# rail_crossing.net
KiCad netlist of a schematic drawn in EAGLE
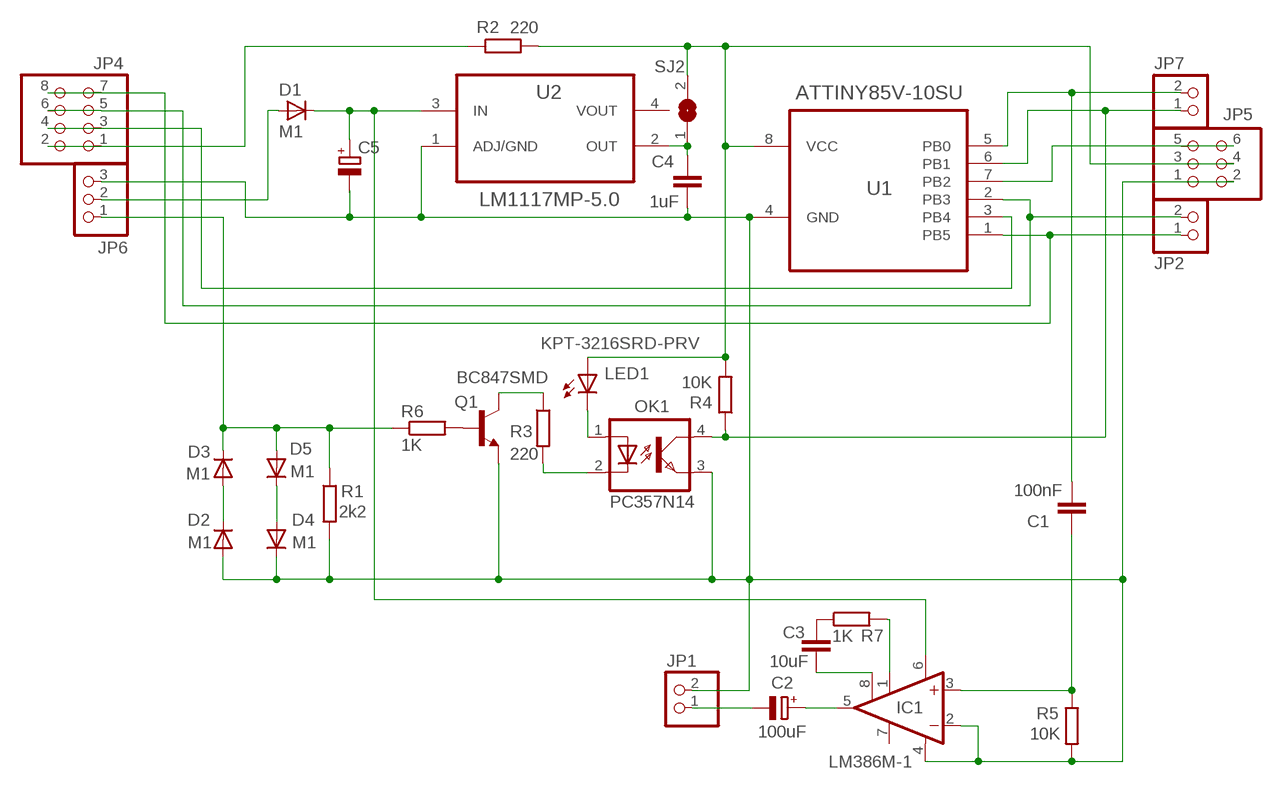
[diagram p0: schematic, sheet 1]

(export (version "E")
  (design (tool "Eeschema 10.0.6"))
  (components
    (comp (ref "C1")
      (value "100nF")
      (footprint "eagle-import:C1206")
      (libsource (lib "eagle-import") (part "C-EUC1206"))
    )
    (comp (ref "C2")
      (value "100uF")
      (footprint "eagle-import:SMC_C")
      (libsource (lib "eagle-import") (part "CPOL-EUSMCC"))
    )
    (comp (ref "C3")
      (value "10uF")
      (footprint "eagle-import:C1206")
      (libsource (lib "eagle-import") (part "C-EUC1206"))
    )
    (comp (ref "C4")
      (value "1uF")
      (footprint "eagle-import:C0402")
      (libsource (lib "eagle-import") (part "C-EUC0402"))
    )
    (comp (ref "C5")
      (value "CPOL-EUSMCD")
      (footprint "eagle-import:SMC_D")
      (libsource (lib "eagle-import") (part "CPOL-EUSMCD"))
    )
    (comp (ref "D1")
      (value "M1")
      (footprint "eagle-import:SMB")
      (libsource (lib "eagle-import") (part "ES2D"))
    )
    (comp (ref "D2")
      (value "M1")
      (footprint "eagle-import:SMB")
      (libsource (lib "eagle-import") (part "ES2D"))
    )
    (comp (ref "D3")
      (value "M1")
      (footprint "eagle-import:SMB")
      (libsource (lib "eagle-import") (part "ES2D"))
    )
    (comp (ref "D4")
      (value "M1")
      (footprint "eagle-import:SMB")
      (libsource (lib "eagle-import") (part "ES2D"))
    )
    (comp (ref "D5")
      (value "M1")
      (footprint "eagle-import:SMB")
      (libsource (lib "eagle-import") (part "ES2D"))
    )
    (comp (ref "IC1")
      (value "LM386M-1")
      (footprint "eagle-import:SO08")
      (libsource (lib "eagle-import") (part "LM386?-M1"))
    )
    (comp (ref "JP1")
      (value "PINHD-1X2/90")
      (footprint "eagle-import:1X02_90")
      (libsource (lib "eagle-import") (part "PINHD-1X2/90"))
    )
    (comp (ref "JP2")
      (value "PINHD-1X2/90")
      (footprint "eagle-import:1X02_90")
      (libsource (lib "eagle-import") (part "PINHD-1X2/90"))
    )
    (comp (ref "JP4")
      (value "PINHD-2X4/90")
      (footprint "eagle-import:2X04_90")
      (libsource (lib "eagle-import") (part "PINHD-2X4/90"))
    )
    (comp (ref "JP5")
      (value "PINHD-2X3/90")
      (footprint "eagle-import:2X03_90")
      (libsource (lib "eagle-import") (part "PINHD-2X3/90"))
    )
    (comp (ref "JP6")
      (value "PINHD-1X3/90")
      (footprint "eagle-import:1X03_90")
      (libsource (lib "eagle-import") (part "PINHD-1X3/90"))
    )
    (comp (ref "JP7")
      (value "PINHD-1X2/90")
      (footprint "eagle-import:1X02_90")
      (libsource (lib "eagle-import") (part "PINHD-1X2/90"))
    )
    (comp (ref "LED1")
      (value "KPT-3216SRD-PRV")
      (footprint "eagle-import:SML1206")
      (libsource (lib "eagle-import") (part "LEDSML1206"))
    )
    (comp (ref "OK1")
      (value "PC357N14")
      (footprint "eagle-import:SMD4")
      (libsource (lib "eagle-import") (part "LTV816S"))
    )
    (comp (ref "Q1")
      (value "BC847SMD")
      (footprint "eagle-import:SOT23")
      (libsource (lib "eagle-import") (part "BC847SMD"))
    )
    (comp (ref "R1")
      (value "2k2")
      (footprint "eagle-import:R1206")
      (libsource (lib "eagle-import") (part "R-EU_R1206"))
    )
    (comp (ref "R2")
      (value "220")
      (footprint "eagle-import:R1206")
      (libsource (lib "eagle-import") (part "R-EU_R1206"))
    )
    (comp (ref "R3")
      (value "220")
      (footprint "eagle-import:R1206")
      (libsource (lib "eagle-import") (part "R-EU_R1206"))
    )
    (comp (ref "R4")
      (value "10K")
      (footprint "eagle-import:R1206")
      (libsource (lib "eagle-import") (part "R-EU_R1206"))
    )
    (comp (ref "R5")
      (value "10K")
      (footprint "eagle-import:R1206")
      (libsource (lib "eagle-import") (part "R-EU_R1206"))
    )
    (comp (ref "R6")
      (value "1K")
      (footprint "eagle-import:R1206")
      (libsource (lib "eagle-import") (part "R-EU_R1206"))
    )
    (comp (ref "R7")
      (value "1K")
      (footprint "eagle-import:M1206")
      (libsource (lib "eagle-import") (part "R-EU_M1206"))
    )
    (comp (ref "SJ2") (value "SJ") (footprint "eagle-import:SJ") (libsource (lib "eagle-import") (part "SJ")))
    (comp (ref "U1")
      (value "ATTINY85V-10SU")
      (footprint "eagle-import:SOIC127P798X216-8N")
      (libsource (lib "eagle-import") (part "ATTINY85V-10SU"))
    )
    (comp (ref "U2")
      (value "LM1117MP-5.0")
      (footprint "eagle-import:SOT230P696X180-4N")
      (libsource (lib "eagle-import") (part "LM1117MP-5.0"))
    )
  )
  (nets
    (net (code "1") (name "Net-(C2-Pad-)") (class "Default")
      (node (ref "C2") (pin "-") (pinfunction "-_-") (pintype "passive"))
      (node (ref "JP1") (pin "1") (pinfunction "1_1") (pintype "passive"))
    )
    (net (code "2") (name "Net-(C3-Pad1)") (class "Default")
      (node (ref "C3") (pin "1") (pinfunction "1_1") (pintype "passive"))
      (node (ref "R7") (pin "1") (pinfunction "1_1") (pintype "passive"))
    )
    (net (code "3") (name "Net-(C3-Pad2)") (class "Default")
      (node (ref "C3") (pin "2") (pinfunction "2_2") (pintype "passive"))
      (node (ref "IC1") (pin "8") (pinfunction "GAIN_8") (pintype "passive"))
    )
    (net (code "4") (name "Net-(D1-PadA)") (class "Default")
      (node (ref "D1") (pin "A") (pinfunction "A_A") (pintype "passive"))
      (node (ref "JP6") (pin "2") (pinfunction "2_2") (pintype "passive"))
    )
    (net (code "5") (name "Net-(D2-PadC)") (class "Default")
      (node (ref "D2") (pin "C") (pinfunction "C_C") (pintype "passive"))
      (node (ref "D3") (pin "A") (pinfunction "A_A") (pintype "passive"))
    )
    (net (code "6") (name "Net-(D3-PadC)") (class "Default")
      (node (ref "D3") (pin "C") (pinfunction "C_C") (pintype "passive"))
      (node (ref "D5") (pin "A") (pinfunction "A_A") (pintype "passive"))
      (node (ref "JP6") (pin "1") (pinfunction "1_1") (pintype "passive"))
      (node (ref "R1") (pin "1") (pinfunction "1_1") (pintype "passive"))
      (node (ref "R6") (pin "1") (pinfunction "1_1") (pintype "passive"))
    )
    (net (code "7") (name "Net-(D4-PadA)") (class "Default")
      (node (ref "D4") (pin "A") (pinfunction "A_A") (pintype "passive"))
      (node (ref "D5") (pin "C") (pinfunction "C_C") (pintype "passive"))
    )
    (net (code "8") (name "Net-(IC1-+IN)") (class "Default")
      (node (ref "C1") (pin "2") (pinfunction "2_2") (pintype "passive"))
      (node (ref "IC1") (pin "3") (pinfunction "+IN_3") (pintype "input"))
      (node (ref "R5") (pin "1") (pinfunction "1_1") (pintype "passive"))
    )
    (net (code "9") (name "Net-(IC1--IN)") (class "Default")
      (node (ref "C4") (pin "2") (pinfunction "2_2") (pintype "passive"))
      (node (ref "D2") (pin "A") (pinfunction "A_A") (pintype "passive"))
      (node (ref "D4") (pin "C") (pinfunction "C_C") (pintype "passive"))
      (node (ref "IC1") (pin "2") (pinfunction "-IN_2") (pintype "input"))
      (node (ref "IC1") (pin "4") (pinfunction "GND_4") (pintype "power_in"))
      (node (ref "JP1") (pin "2") (pinfunction "2_2") (pintype "passive"))
      (node (ref "JP5") (pin "1") (pinfunction "1_1") (pintype "passive"))
      (node (ref "JP5") (pin "2") (pinfunction "2_2") (pintype "passive"))
      (node (ref "JP6") (pin "3") (pinfunction "3_3") (pintype "passive"))
      (node (ref "OK1") (pin "3") (pinfunction "EMIT_3") (pintype "passive"))
      (node (ref "Q1") (pin "2") (pinfunction "E_2") (pintype "passive"))
      (node (ref "R1") (pin "2") (pinfunction "2_2") (pintype "passive"))
      (node (ref "R5") (pin "2") (pinfunction "2_2") (pintype "passive"))
      (node (ref "U1") (pin "4") (pinfunction "GND_4") (pintype "passive"))
      (node (ref "U2") (pin "1") (pinfunction "ADJ/GND_1") (pintype "passive"))
    )
    (net (code "10") (name "Net-(IC1-GAIN-Pad1)") (class "Default")
      (node (ref "IC1") (pin "1") (pinfunction "GAIN_1") (pintype "passive"))
      (node (ref "R7") (pin "2") (pinfunction "2_2") (pintype "passive"))
    )
    (net (code "11") (name "Net-(IC1-OUT)") (class "Default")
      (node (ref "C2") (pin "+") (pinfunction "+_+") (pintype "passive"))
      (node (ref "IC1") (pin "5") (pinfunction "OUT_5") (pintype "output"))
    )
    (net (code "12") (name "Net-(IC1-VS)") (class "Default")
      (node (ref "C5") (pin "+") (pinfunction "+_+") (pintype "passive"))
      (node (ref "D1") (pin "C") (pinfunction "C_C") (pintype "passive"))
      (node (ref "IC1") (pin "6") (pinfunction "VS_6") (pintype "power_in"))
      (node (ref "U2") (pin "3") (pinfunction "IN_3") (pintype "input"))
    )
    (net (code "13") (name "Net-(JP4-Pad1)") (class "Default")
      (node (ref "JP4") (pin "1") (pinfunction "1_1") (pintype "passive"))
      (node (ref "JP4") (pin "2") (pinfunction "2_2") (pintype "passive"))
      (node (ref "R2") (pin "1") (pinfunction "1_1") (pintype "passive"))
    )
    (net (code "14") (name "Net-(OK1-A)") (class "Default")
      (node (ref "LED1") (pin "C") (pinfunction "C_C") (pintype "passive"))
      (node (ref "OK1") (pin "1") (pinfunction "A_1") (pintype "passive"))
    )
    (net (code "15") (name "Net-(OK1-C)") (class "Default")
      (node (ref "OK1") (pin "2") (pinfunction "C_2") (pintype "passive"))
      (node (ref "R3") (pin "2") (pinfunction "2_2") (pintype "passive"))
    )
    (net (code "16") (name "Net-(OK1-COL)") (class "Default")
      (node (ref "JP7") (pin "1") (pinfunction "1_1") (pintype "passive"))
      (node (ref "OK1") (pin "4") (pinfunction "COL_4") (pintype "passive"))
      (node (ref "R4") (pin "1") (pinfunction "1_1") (pintype "passive"))
      (node (ref "U1") (pin "6") (pinfunction "PB1_6") (pintype "bidirectional"))
    )
    (net (code "17") (name "Net-(Q1-B)") (class "Default")
      (node (ref "Q1") (pin "1") (pinfunction "B_1") (pintype "passive"))
      (node (ref "R6") (pin "2") (pinfunction "2_2") (pintype "passive"))
    )
    (net (code "18") (name "Net-(Q1-C)") (class "Default")
      (node (ref "Q1") (pin "3") (pinfunction "C_3") (pintype "passive"))
      (node (ref "R3") (pin "1") (pinfunction "1_1") (pintype "passive"))
    )
    (net (code "19") (name "Net-(U1-PB0)") (class "Default")
      (node (ref "C1") (pin "1") (pinfunction "1_1") (pintype "passive"))
      (node (ref "JP7") (pin "2") (pinfunction "2_2") (pintype "passive"))
      (node (ref "U1") (pin "5") (pinfunction "PB0_5") (pintype "bidirectional"))
    )
    (net (code "20") (name "Net-(U1-PB2)") (class "Default")
      (node (ref "JP5") (pin "5") (pinfunction "5_5") (pintype "passive"))
      (node (ref "JP5") (pin "6") (pinfunction "6_6") (pintype "passive"))
      (node (ref "U1") (pin "7") (pinfunction "PB2_7") (pintype "bidirectional"))
    )
    (net (code "21") (name "Net-(U1-PB3)") (class "Default")
      (node (ref "JP2") (pin "2") (pinfunction "2_2") (pintype "passive"))
      (node (ref "JP4") (pin "5") (pinfunction "5_5") (pintype "passive"))
      (node (ref "JP4") (pin "6") (pinfunction "6_6") (pintype "passive"))
      (node (ref "U1") (pin "2") (pinfunction "PB3_2") (pintype "bidirectional"))
    )
    (net (code "22") (name "Net-(U1-PB4)") (class "Default")
      (node (ref "JP4") (pin "3") (pinfunction "3_3") (pintype "passive"))
      (node (ref "JP4") (pin "4") (pinfunction "4_4") (pintype "passive"))
      (node (ref "U1") (pin "3") (pinfunction "PB4_3") (pintype "bidirectional"))
    )
    (net (code "23") (name "Net-(U1-PB5)") (class "Default")
      (node (ref "JP2") (pin "1") (pinfunction "1_1") (pintype "passive"))
      (node (ref "JP4") (pin "7") (pinfunction "7_7") (pintype "passive"))
      (node (ref "JP4") (pin "8") (pinfunction "8_8") (pintype "passive"))
      (node (ref "U1") (pin "1") (pinfunction "PB5_1") (pintype "bidirectional"))
    )
    (net (code "24") (name "Net-(U1-VCC)") (class "Default")
      (node (ref "JP5") (pin "3") (pinfunction "3_3") (pintype "passive"))
      (node (ref "JP5") (pin "4") (pinfunction "4_4") (pintype "passive"))
      (node (ref "LED1") (pin "A") (pinfunction "A_A") (pintype "passive"))
      (node (ref "R2") (pin "2") (pinfunction "2_2") (pintype "passive"))
      (node (ref "R4") (pin "2") (pinfunction "2_2") (pintype "passive"))
      (node (ref "SJ2") (pin "2") (pinfunction "2_2") (pintype "passive"))
      (node (ref "U1") (pin "8") (pinfunction "VCC_8") (pintype "power_in"))
    )
    (net (code "25") (name "Net-(U2-OUT)") (class "Default")
      (node (ref "C4") (pin "1") (pinfunction "1_1") (pintype "passive"))
      (node (ref "SJ2") (pin "1") (pinfunction "1_1") (pintype "passive"))
      (node (ref "U2") (pin "2") (pinfunction "OUT_2") (pintype "output"))
    )
    (net (code "26") (name "unconnected-(C5-Pad-)") (class "Default")
      (node (ref "C5") (pin "-") (pinfunction "-_-") (pintype "passive"))
    )
    (net (code "27") (name "unconnected-(IC1-BYPASS-Pad7)") (class "Default")
      (node (ref "IC1") (pin "7") (pinfunction "BYPASS_7") (pintype "passive"))
    )
    (net (code "28") (name "unconnected-(U2-VOUT-Pad4)") (class "Default")
      (node (ref "U2") (pin "4") (pinfunction "VOUT_4") (pintype "output"))
    )
  )
)
